# 1_byte_output.net
KiCad netlist of a schematic drawn in EAGLE
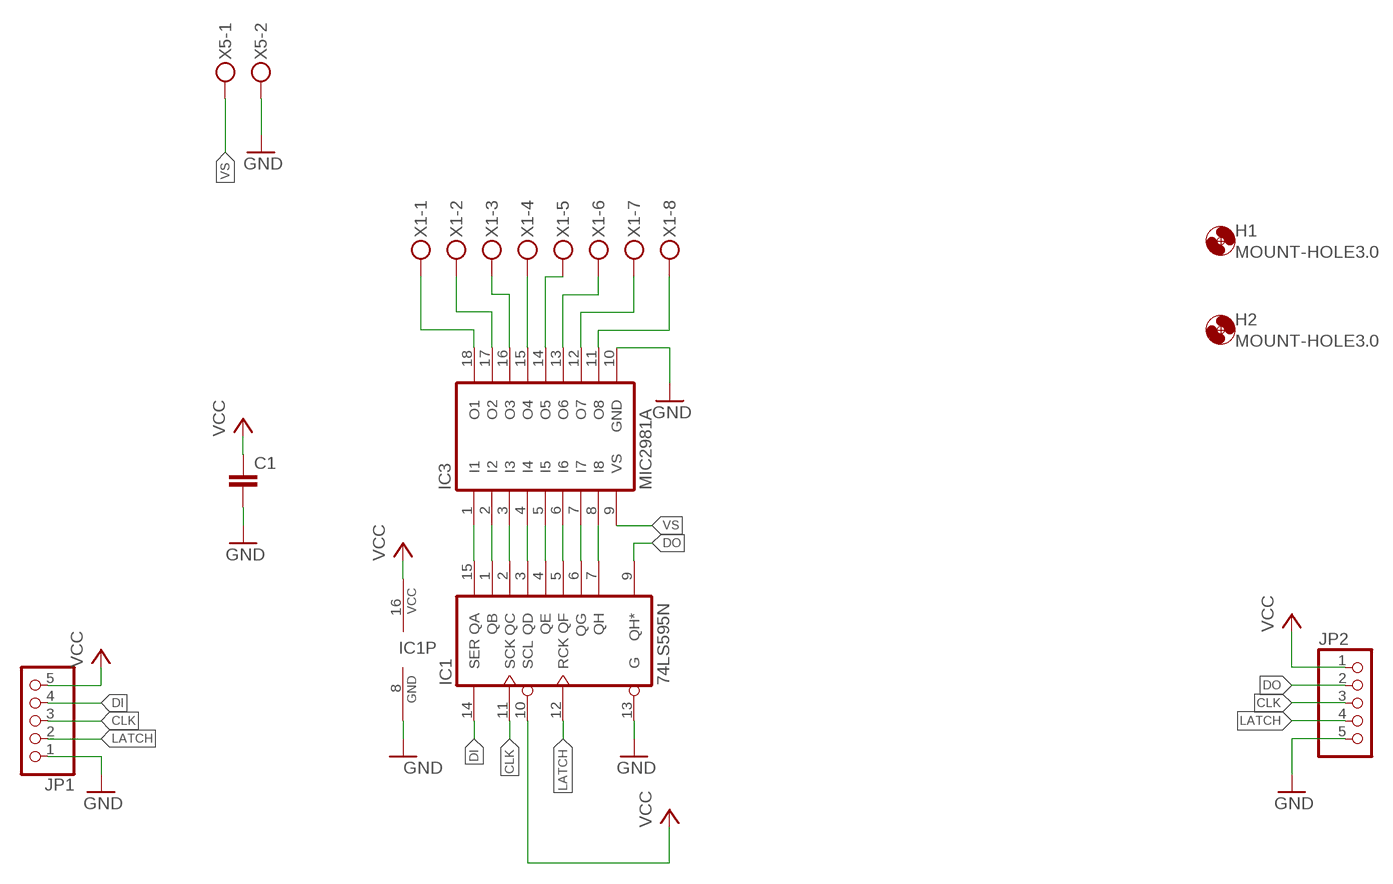
[diagram p0: schematic, sheet 1]

(export (version "E")
  (design (tool "Eeschema 10.0.6"))
  (components
    (comp (ref "C1")
      (value "C-EU050-035X075")
      (footprint "eagle-import:C050-035X075")
      (libsource (lib "eagle-import") (part "C-EU050-035X075"))
    )
    (comp (ref "H1")
      (value "MOUNT-HOLE3.0")
      (footprint "eagle-import:3,0")
      (libsource (lib "eagle-import") (part "MOUNT-HOLE3.0"))
    )
    (comp (ref "H2")
      (value "MOUNT-HOLE3.0")
      (footprint "eagle-import:3,0")
      (libsource (lib "eagle-import") (part "MOUNT-HOLE3.0"))
    )
    (comp (ref "IC1")
      (value "74LS595N")
      (footprint "eagle-import:DIL16")
      (libsource (lib "eagle-import") (part "74595NLS"))
    )
    (comp (ref "IC3")
      (value "MIC2981A")
      (footprint "eagle-import:DIL18")
      (libsource (lib "eagle-import") (part "UDN298A1"))
    )
    (comp (ref "JP1")
      (value "PINHD-1X5/90")
      (footprint "eagle-import:1X05_90")
      (libsource (lib "eagle-import") (part "PINHD-1X5/90"))
    )
    (comp (ref "JP2")
      (value "PINHD-1X5/90")
      (footprint "eagle-import:1X05_90")
      (libsource (lib "eagle-import") (part "PINHD-1X5/90"))
    )
    (comp (ref "X1")
      (value "MKDSN1,5/8-5,08")
      (footprint "eagle-import:MKDSN1,5_8-5,08")
      (libsource (lib "eagle-import") (part "MKDSN1,5/8-5,08"))
    )
    (comp (ref "X5")
      (value "MKDSN1,5/2-5,08")
      (footprint "eagle-import:MKDSN1,5_2-5,08")
      (libsource (lib "eagle-import") (part "MKDSN1,5/2-5,08"))
    )
  )
  (nets
    (net (code "1") (name "CLK") (class "Default")
      (node (ref "IC1") (pin "11") (pinfunction "SCK_11") (pintype "input"))
      (node (ref "JP1") (pin "3") (pinfunction "3_3") (pintype "passive"))
      (node (ref "JP2") (pin "3") (pinfunction "3_3") (pintype "passive"))
    )
    (net (code "2") (name "DI") (class "Default")
      (node (ref "IC1") (pin "14") (pinfunction "SER_14") (pintype "input"))
      (node (ref "JP1") (pin "4") (pinfunction "4_4") (pintype "passive"))
    )
    (net (code "3") (name "DO") (class "Default")
      (node (ref "IC1") (pin "9") (pinfunction "QH*_9") (pintype "tri_state"))
      (node (ref "JP2") (pin "2") (pinfunction "2_2") (pintype "passive"))
    )
    (net (code "4") (name "GND") (class "Default")
      (node (ref "C1") (pin "2") (pinfunction "2_2") (pintype "passive"))
      (node (ref "IC1") (pin "13") (pinfunction "G_13") (pintype "input"))
      (node (ref "IC1") (pin "8") (pinfunction "GND_8") (pintype "power_in"))
      (node (ref "IC3") (pin "10") (pinfunction "GND_10") (pintype "power_in"))
      (node (ref "JP1") (pin "1") (pinfunction "1_1") (pintype "passive"))
      (node (ref "JP2") (pin "5") (pinfunction "5_5") (pintype "passive"))
      (node (ref "X5") (pin "2") (pinfunction "KL_2") (pintype "passive"))
    )
    (net (code "5") (name "LATCH") (class "Default")
      (node (ref "IC1") (pin "12") (pinfunction "RCK_12") (pintype "input"))
      (node (ref "JP1") (pin "2") (pinfunction "2_2") (pintype "passive"))
      (node (ref "JP2") (pin "4") (pinfunction "4_4") (pintype "passive"))
    )
    (net (code "6") (name "Net-(IC1A-QA)") (class "Default")
      (node (ref "IC1") (pin "15") (pinfunction "QA_15") (pintype "tri_state"))
      (node (ref "IC3") (pin "1") (pinfunction "I1_1") (pintype "input"))
    )
    (net (code "7") (name "Net-(IC1A-QB)") (class "Default")
      (node (ref "IC1") (pin "1") (pinfunction "QB_1") (pintype "tri_state"))
      (node (ref "IC3") (pin "2") (pinfunction "I2_2") (pintype "input"))
    )
    (net (code "8") (name "Net-(IC1A-QC)") (class "Default")
      (node (ref "IC1") (pin "2") (pinfunction "QC_2") (pintype "tri_state"))
      (node (ref "IC3") (pin "3") (pinfunction "I3_3") (pintype "input"))
    )
    (net (code "9") (name "Net-(IC1A-QD)") (class "Default")
      (node (ref "IC1") (pin "3") (pinfunction "QD_3") (pintype "tri_state"))
      (node (ref "IC3") (pin "4") (pinfunction "I4_4") (pintype "input"))
    )
    (net (code "10") (name "Net-(IC1A-QE)") (class "Default")
      (node (ref "IC1") (pin "4") (pinfunction "QE_4") (pintype "tri_state"))
      (node (ref "IC3") (pin "5") (pinfunction "I5_5") (pintype "input"))
    )
    (net (code "11") (name "Net-(IC1A-QF)") (class "Default")
      (node (ref "IC1") (pin "5") (pinfunction "QF_5") (pintype "tri_state"))
      (node (ref "IC3") (pin "6") (pinfunction "I6_6") (pintype "input"))
    )
    (net (code "12") (name "Net-(IC1A-QG)") (class "Default")
      (node (ref "IC1") (pin "6") (pinfunction "QG_6") (pintype "tri_state"))
      (node (ref "IC3") (pin "7") (pinfunction "I7_7") (pintype "input"))
    )
    (net (code "13") (name "Net-(IC1A-QH)") (class "Default")
      (node (ref "IC1") (pin "7") (pinfunction "QH_7") (pintype "tri_state"))
      (node (ref "IC3") (pin "8") (pinfunction "I8_8") (pintype "input"))
    )
    (net (code "14") (name "Net-(IC3-O1)") (class "Default")
      (node (ref "IC3") (pin "18") (pinfunction "O1_18") (pintype "open_collector"))
      (node (ref "X1") (pin "1") (pinfunction "KL_1") (pintype "passive"))
    )
    (net (code "15") (name "Net-(IC3-O2)") (class "Default")
      (node (ref "IC3") (pin "17") (pinfunction "O2_17") (pintype "open_collector"))
      (node (ref "X1") (pin "2") (pinfunction "KL_2") (pintype "passive"))
    )
    (net (code "16") (name "Net-(IC3-O3)") (class "Default")
      (node (ref "IC3") (pin "16") (pinfunction "O3_16") (pintype "open_collector"))
      (node (ref "X1") (pin "3") (pinfunction "KL_3") (pintype "passive"))
    )
    (net (code "17") (name "Net-(IC3-O4)") (class "Default")
      (node (ref "IC3") (pin "15") (pinfunction "O4_15") (pintype "open_collector"))
      (node (ref "X1") (pin "4") (pinfunction "KL_4") (pintype "passive"))
    )
    (net (code "18") (name "Net-(IC3-O5)") (class "Default")
      (node (ref "IC3") (pin "14") (pinfunction "O5_14") (pintype "open_collector"))
      (node (ref "X1") (pin "5") (pinfunction "KL_5") (pintype "passive"))
    )
    (net (code "19") (name "Net-(IC3-O6)") (class "Default")
      (node (ref "IC3") (pin "13") (pinfunction "O6_13") (pintype "open_collector"))
      (node (ref "X1") (pin "6") (pinfunction "KL_6") (pintype "passive"))
    )
    (net (code "20") (name "Net-(IC3-O7)") (class "Default")
      (node (ref "IC3") (pin "12") (pinfunction "O7_12") (pintype "open_collector"))
      (node (ref "X1") (pin "7") (pinfunction "KL_7") (pintype "passive"))
    )
    (net (code "21") (name "Net-(IC3-O8)") (class "Default")
      (node (ref "IC3") (pin "11") (pinfunction "O8_11") (pintype "open_collector"))
      (node (ref "X1") (pin "8") (pinfunction "KL_8") (pintype "passive"))
    )
    (net (code "22") (name "VCC") (class "Default")
      (node (ref "C1") (pin "1") (pinfunction "1_1") (pintype "passive"))
      (node (ref "IC1") (pin "10") (pinfunction "SCL_10") (pintype "input"))
      (node (ref "IC1") (pin "16") (pinfunction "VCC_16") (pintype "power_in"))
      (node (ref "JP1") (pin "5") (pinfunction "5_5") (pintype "passive"))
      (node (ref "JP2") (pin "1") (pinfunction "1_1") (pintype "passive"))
    )
    (net (code "23") (name "VS") (class "Default")
      (node (ref "IC3") (pin "9") (pinfunction "VS_9") (pintype "passive"))
      (node (ref "X5") (pin "1") (pinfunction "KL_1") (pintype "passive"))
    )
  )
)
